# MIPI_CSI-2.net
KiCad netlist of a schematic drawn in Altium Designer
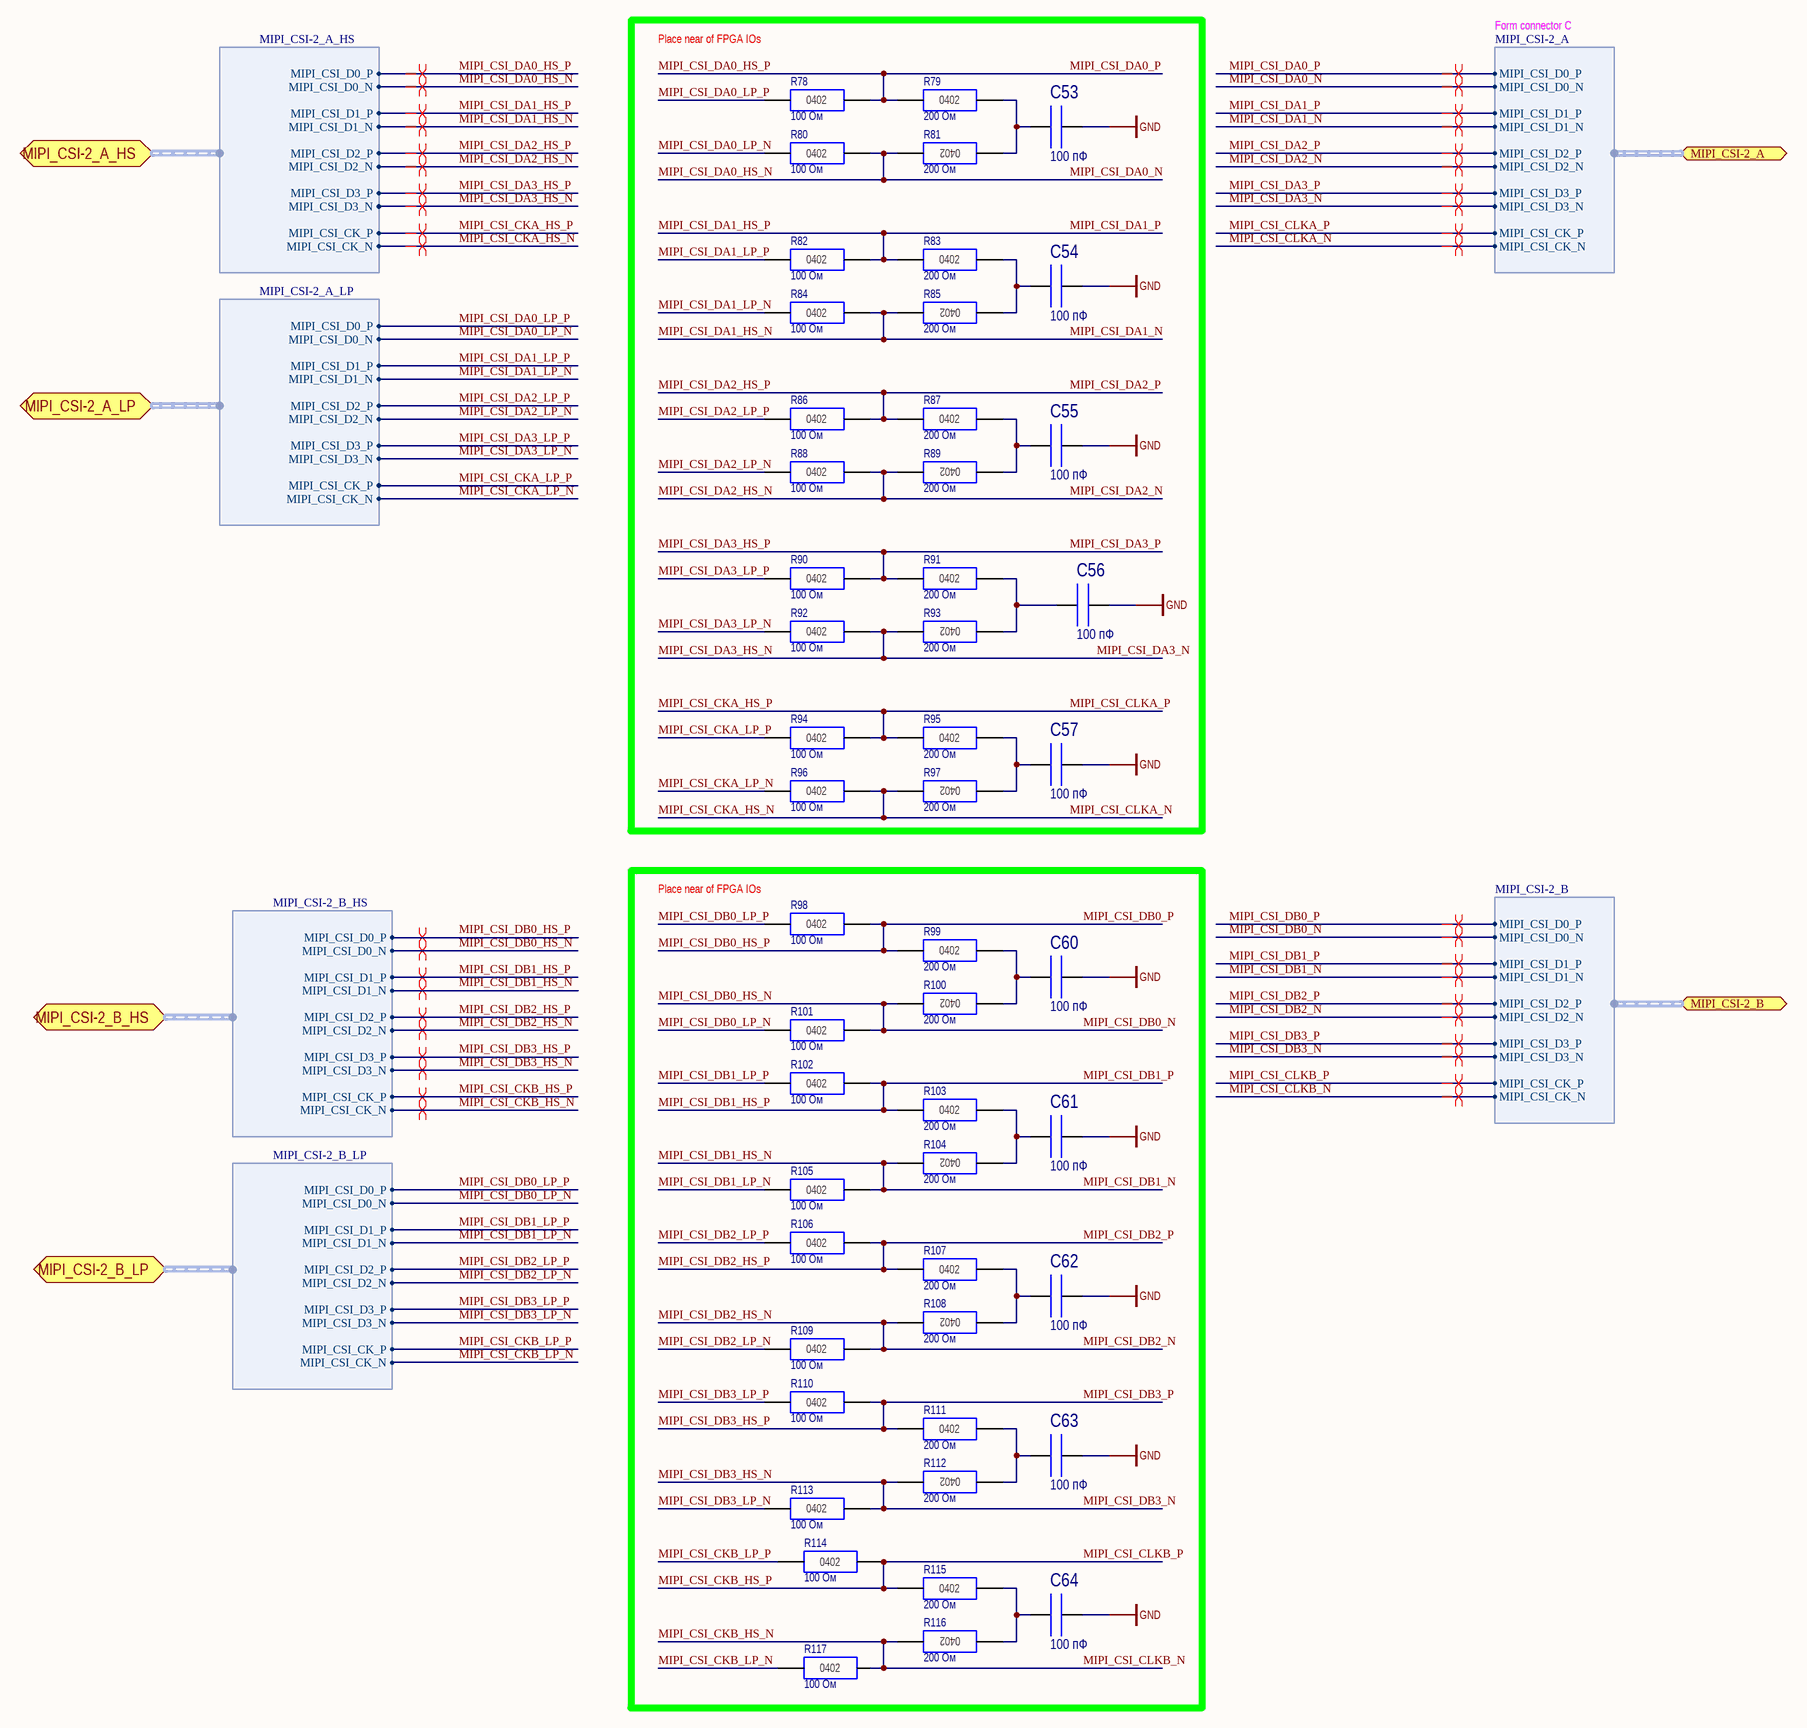
[diagram p0: MIPI_CSI-2.SchDoc]

(export (version "E")
  (design (tool "Eeschema 10.0.6"))
  (components
    (comp (ref "C53")
      (value "100 пФ")
      (footprint "CC0402(1005)")
      (description "Чип конденсатор керамический")
      (fields (field (name "Comment") "CC0402-NP0-100 пФ-1%-50В"))
      (libsource (lib "Чип конденсаторы") (part "CC0402-X7R-#-20%-10В"))
    )
    (comp (ref "C54")
      (value "100 пФ")
      (footprint "CC0402(1005)")
      (description "Чип конденсатор керамический")
      (fields (field (name "Comment") "CC0402-NP0-100 пФ-1%-50В"))
      (libsource (lib "Чип конденсаторы") (part "CC0402-X7R-#-20%-10В"))
    )
    (comp (ref "C55")
      (value "100 пФ")
      (footprint "CC0402(1005)")
      (description "Чип конденсатор керамический")
      (fields (field (name "Comment") "CC0402-NP0-100 пФ-1%-50В"))
      (libsource (lib "Чип конденсаторы") (part "CC0402-X7R-#-20%-10В"))
    )
    (comp (ref "C56")
      (value "100 пФ")
      (footprint "CC0402(1005)")
      (description "Чип конденсатор керамический")
      (fields (field (name "Comment") "CC0402-NP0-100 пФ-1%-50В"))
      (libsource (lib "Чип конденсаторы") (part "CC0402-X7R-#-20%-10В"))
    )
    (comp (ref "C57")
      (value "100 пФ")
      (footprint "CC0402(1005)")
      (description "Чип конденсатор керамический")
      (fields (field (name "Comment") "CC0402-NP0-100 пФ-1%-50В"))
      (libsource (lib "Чип конденсаторы") (part "CC0402-X7R-#-20%-10В"))
    )
    (comp (ref "C60")
      (value "100 пФ")
      (footprint "CC0402(1005)")
      (description "Чип конденсатор керамический")
      (fields (field (name "Comment") "CC0402-NP0-100 пФ-1%-50В"))
      (libsource (lib "Чип конденсаторы") (part "CC0402-X7R-#-20%-10В"))
    )
    (comp (ref "C61")
      (value "100 пФ")
      (footprint "CC0402(1005)")
      (description "Чип конденсатор керамический")
      (fields (field (name "Comment") "CC0402-NP0-100 пФ-1%-50В"))
      (libsource (lib "Чип конденсаторы") (part "CC0402-X7R-#-20%-10В"))
    )
    (comp (ref "C62")
      (value "100 пФ")
      (footprint "CC0402(1005)")
      (description "Чип конденсатор керамический")
      (fields (field (name "Comment") "CC0402-NP0-100 пФ-1%-50В"))
      (libsource (lib "Чип конденсаторы") (part "CC0402-X7R-#-20%-10В"))
    )
    (comp (ref "C63")
      (value "100 пФ")
      (footprint "CC0402(1005)")
      (description "Чип конденсатор керамический")
      (fields (field (name "Comment") "CC0402-NP0-100 пФ-1%-50В"))
      (libsource (lib "Чип конденсаторы") (part "CC0402-X7R-#-20%-10В"))
    )
    (comp (ref "C64")
      (value "100 пФ")
      (footprint "CC0402(1005)")
      (description "Чип конденсатор керамический")
      (fields (field (name "Comment") "CC0402-NP0-100 пФ-1%-50В"))
      (libsource (lib "Чип конденсаторы") (part "CC0402-X7R-#-20%-10В"))
    )
    (comp (ref "R78")
      (value "100 Ом")
      (footprint "CR0402(1005)")
      (description "Чип резистор")
      (fields (field (name "TOLERANCE") "5%") (field (name "Comment") "CR0402-100 Ом-±5%"))
      (libsource (lib "") (part "CR0402-#-±5%_1"))
    )
    (comp (ref "R79")
      (value "200 Ом")
      (footprint "CR0402(1005)")
      (description "Чип резистор")
      (fields (field (name "TOLERANCE") "5%") (field (name "Comment") "CR0402-200 Ом-±5%"))
      (libsource (lib "") (part "CR0402-#-±5%_1"))
    )
    (comp (ref "R80")
      (value "100 Ом")
      (footprint "CR0402(1005)")
      (description "Чип резистор")
      (fields (field (name "TOLERANCE") "5%") (field (name "Comment") "CR0402-100 Ом-±5%"))
      (libsource (lib "") (part "CR0402-#-±5%_1"))
    )
    (comp (ref "R81")
      (value "200 Ом")
      (footprint "CR0402(1005)")
      (description "Чип резистор")
      (fields (field (name "TOLERANCE") "5%") (field (name "Comment") "CR0402-200 Ом-±5%"))
      (libsource (lib "Резисторы") (part "CR0402-#-±5%"))
    )
    (comp (ref "R82")
      (value "100 Ом")
      (footprint "CR0402(1005)")
      (description "Чип резистор")
      (fields (field (name "TOLERANCE") "5%") (field (name "Comment") "CR0402-100 Ом-±5%"))
      (libsource (lib "") (part "CR0402-#-±5%_1"))
    )
    (comp (ref "R83")
      (value "200 Ом")
      (footprint "CR0402(1005)")
      (description "Чип резистор")
      (fields (field (name "TOLERANCE") "5%") (field (name "Comment") "CR0402-200 Ом-±5%"))
      (libsource (lib "") (part "CR0402-#-±5%_1"))
    )
    (comp (ref "R84")
      (value "100 Ом")
      (footprint "CR0402(1005)")
      (description "Чип резистор")
      (fields (field (name "TOLERANCE") "5%") (field (name "Comment") "CR0402-100 Ом-±5%"))
      (libsource (lib "") (part "CR0402-#-±5%_1"))
    )
    (comp (ref "R85")
      (value "200 Ом")
      (footprint "CR0402(1005)")
      (description "Чип резистор")
      (fields (field (name "TOLERANCE") "5%") (field (name "Comment") "CR0402-200 Ом-±5%"))
      (libsource (lib "Резисторы") (part "CR0402-#-±5%"))
    )
    (comp (ref "R86")
      (value "100 Ом")
      (footprint "CR0402(1005)")
      (description "Чип резистор")
      (fields (field (name "TOLERANCE") "5%") (field (name "Comment") "CR0402-100 Ом-±5%"))
      (libsource (lib "") (part "CR0402-#-±5%_1"))
    )
    (comp (ref "R87")
      (value "200 Ом")
      (footprint "CR0402(1005)")
      (description "Чип резистор")
      (fields (field (name "TOLERANCE") "5%") (field (name "Comment") "CR0402-200 Ом-±5%"))
      (libsource (lib "") (part "CR0402-#-±5%_1"))
    )
    (comp (ref "R88")
      (value "100 Ом")
      (footprint "CR0402(1005)")
      (description "Чип резистор")
      (fields (field (name "TOLERANCE") "5%") (field (name "Comment") "CR0402-100 Ом-±5%"))
      (libsource (lib "") (part "CR0402-#-±5%_1"))
    )
    (comp (ref "R89")
      (value "200 Ом")
      (footprint "CR0402(1005)")
      (description "Чип резистор")
      (fields (field (name "TOLERANCE") "5%") (field (name "Comment") "CR0402-200 Ом-±5%"))
      (libsource (lib "Резисторы") (part "CR0402-#-±5%"))
    )
    (comp (ref "R90")
      (value "100 Ом")
      (footprint "CR0402(1005)")
      (description "Чип резистор")
      (fields (field (name "TOLERANCE") "5%") (field (name "Comment") "CR0402-100 Ом-±5%"))
      (libsource (lib "") (part "CR0402-#-±5%_1"))
    )
    (comp (ref "R91")
      (value "200 Ом")
      (footprint "CR0402(1005)")
      (description "Чип резистор")
      (fields (field (name "TOLERANCE") "5%") (field (name "Comment") "CR0402-200 Ом-±5%"))
      (libsource (lib "") (part "CR0402-#-±5%_1"))
    )
    (comp (ref "R92")
      (value "100 Ом")
      (footprint "CR0402(1005)")
      (description "Чип резистор")
      (fields (field (name "TOLERANCE") "5%") (field (name "Comment") "CR0402-100 Ом-±5%"))
      (libsource (lib "") (part "CR0402-#-±5%_1"))
    )
    (comp (ref "R93")
      (value "200 Ом")
      (footprint "CR0402(1005)")
      (description "Чип резистор")
      (fields (field (name "TOLERANCE") "5%") (field (name "Comment") "CR0402-200 Ом-±5%"))
      (libsource (lib "Резисторы") (part "CR0402-#-±5%"))
    )
    (comp (ref "R94")
      (value "100 Ом")
      (footprint "CR0402(1005)")
      (description "Чип резистор")
      (fields (field (name "TOLERANCE") "5%") (field (name "Comment") "CR0402-100 Ом-±5%"))
      (libsource (lib "") (part "CR0402-#-±5%_1"))
    )
    (comp (ref "R95")
      (value "200 Ом")
      (footprint "CR0402(1005)")
      (description "Чип резистор")
      (fields (field (name "TOLERANCE") "5%") (field (name "Comment") "CR0402-200 Ом-±5%"))
      (libsource (lib "") (part "CR0402-#-±5%_1"))
    )
    (comp (ref "R96")
      (value "100 Ом")
      (footprint "CR0402(1005)")
      (description "Чип резистор")
      (fields (field (name "TOLERANCE") "5%") (field (name "Comment") "CR0402-100 Ом-±5%"))
      (libsource (lib "") (part "CR0402-#-±5%_1"))
    )
    (comp (ref "R97")
      (value "200 Ом")
      (footprint "CR0402(1005)")
      (description "Чип резистор")
      (fields (field (name "TOLERANCE") "5%") (field (name "Comment") "CR0402-200 Ом-±5%"))
      (libsource (lib "Резисторы") (part "CR0402-#-±5%"))
    )
    (comp (ref "R98")
      (value "100 Ом")
      (footprint "CR0402(1005)")
      (description "Чип резистор")
      (fields (field (name "TOLERANCE") "5%") (field (name "Comment") "CR0402-100 Ом-±5%"))
      (libsource (lib "") (part "CR0402-#-±5%_1"))
    )
    (comp (ref "R99")
      (value "200 Ом")
      (footprint "CR0402(1005)")
      (description "Чип резистор")
      (fields (field (name "TOLERANCE") "5%") (field (name "Comment") "CR0402-200 Ом-±5%"))
      (libsource (lib "") (part "CR0402-#-±5%_1"))
    )
    (comp (ref "R100")
      (value "200 Ом")
      (footprint "CR0402(1005)")
      (description "Чип резистор")
      (fields (field (name "TOLERANCE") "5%") (field (name "Comment") "CR0402-200 Ом-±5%"))
      (libsource (lib "Резисторы") (part "CR0402-#-±5%"))
    )
    (comp (ref "R101")
      (value "100 Ом")
      (footprint "CR0402(1005)")
      (description "Чип резистор")
      (fields (field (name "TOLERANCE") "5%") (field (name "Comment") "CR0402-100 Ом-±5%"))
      (libsource (lib "") (part "CR0402-#-±5%_1"))
    )
    (comp (ref "R102")
      (value "100 Ом")
      (footprint "CR0402(1005)")
      (description "Чип резистор")
      (fields (field (name "TOLERANCE") "5%") (field (name "Comment") "CR0402-100 Ом-±5%"))
      (libsource (lib "") (part "CR0402-#-±5%_1"))
    )
    (comp (ref "R103")
      (value "200 Ом")
      (footprint "CR0402(1005)")
      (description "Чип резистор")
      (fields (field (name "TOLERANCE") "5%") (field (name "Comment") "CR0402-200 Ом-±5%"))
      (libsource (lib "") (part "CR0402-#-±5%_1"))
    )
    (comp (ref "R104")
      (value "200 Ом")
      (footprint "CR0402(1005)")
      (description "Чип резистор")
      (fields (field (name "TOLERANCE") "5%") (field (name "Comment") "CR0402-200 Ом-±5%"))
      (libsource (lib "Резисторы") (part "CR0402-#-±5%"))
    )
    (comp (ref "R105")
      (value "100 Ом")
      (footprint "CR0402(1005)")
      (description "Чип резистор")
      (fields (field (name "TOLERANCE") "5%") (field (name "Comment") "CR0402-100 Ом-±5%"))
      (libsource (lib "") (part "CR0402-#-±5%_1"))
    )
    (comp (ref "R106")
      (value "100 Ом")
      (footprint "CR0402(1005)")
      (description "Чип резистор")
      (fields (field (name "TOLERANCE") "5%") (field (name "Comment") "CR0402-100 Ом-±5%"))
      (libsource (lib "") (part "CR0402-#-±5%_1"))
    )
    (comp (ref "R107")
      (value "200 Ом")
      (footprint "CR0402(1005)")
      (description "Чип резистор")
      (fields (field (name "TOLERANCE") "5%") (field (name "Comment") "CR0402-200 Ом-±5%"))
      (libsource (lib "") (part "CR0402-#-±5%_1"))
    )
    (comp (ref "R108")
      (value "200 Ом")
      (footprint "CR0402(1005)")
      (description "Чип резистор")
      (fields (field (name "TOLERANCE") "5%") (field (name "Comment") "CR0402-200 Ом-±5%"))
      (libsource (lib "Резисторы") (part "CR0402-#-±5%"))
    )
    (comp (ref "R109")
      (value "100 Ом")
      (footprint "CR0402(1005)")
      (description "Чип резистор")
      (fields (field (name "TOLERANCE") "5%") (field (name "Comment") "CR0402-100 Ом-±5%"))
      (libsource (lib "") (part "CR0402-#-±5%_1"))
    )
    (comp (ref "R110")
      (value "100 Ом")
      (footprint "CR0402(1005)")
      (description "Чип резистор")
      (fields (field (name "TOLERANCE") "5%") (field (name "Comment") "CR0402-100 Ом-±5%"))
      (libsource (lib "") (part "CR0402-#-±5%_1"))
    )
    (comp (ref "R111")
      (value "200 Ом")
      (footprint "CR0402(1005)")
      (description "Чип резистор")
      (fields (field (name "TOLERANCE") "5%") (field (name "Comment") "CR0402-200 Ом-±5%"))
      (libsource (lib "") (part "CR0402-#-±5%_1"))
    )
    (comp (ref "R112")
      (value "200 Ом")
      (footprint "CR0402(1005)")
      (description "Чип резистор")
      (fields (field (name "TOLERANCE") "5%") (field (name "Comment") "CR0402-200 Ом-±5%"))
      (libsource (lib "Резисторы") (part "CR0402-#-±5%"))
    )
    (comp (ref "R113")
      (value "100 Ом")
      (footprint "CR0402(1005)")
      (description "Чип резистор")
      (fields (field (name "TOLERANCE") "5%") (field (name "Comment") "CR0402-100 Ом-±5%"))
      (libsource (lib "") (part "CR0402-#-±5%_1"))
    )
    (comp (ref "R114")
      (value "100 Ом")
      (footprint "CR0402(1005)")
      (description "Чип резистор")
      (fields (field (name "TOLERANCE") "5%") (field (name "Comment") "CR0402-100 Ом-±5%"))
      (libsource (lib "") (part "CR0402-#-±5%_1"))
    )
    (comp (ref "R115")
      (value "200 Ом")
      (footprint "CR0402(1005)")
      (description "Чип резистор")
      (fields (field (name "TOLERANCE") "5%") (field (name "Comment") "CR0402-200 Ом-±5%"))
      (libsource (lib "") (part "CR0402-#-±5%_1"))
    )
    (comp (ref "R116")
      (value "200 Ом")
      (footprint "CR0402(1005)")
      (description "Чип резистор")
      (fields (field (name "TOLERANCE") "5%") (field (name "Comment") "CR0402-200 Ом-±5%"))
      (libsource (lib "Резисторы") (part "CR0402-#-±5%"))
    )
    (comp (ref "R117")
      (value "100 Ом")
      (footprint "CR0402(1005)")
      (description "Чип резистор")
      (fields (field (name "TOLERANCE") "5%") (field (name "Comment") "CR0402-100 Ом-±5%"))
      (libsource (lib "") (part "CR0402-#-±5%_1"))
    )
  )
  (nets
    (net (code "7") (name "/MIPI_CSI_CKA_HS_N") (class "Default")
      (node (ref "R96") (pin "2") (pinfunction "-_2") (pintype "passive"))
      (node (ref "R97") (pin "2") (pinfunction "-_2") (pintype "passive"))
    )
    (net (code "8") (name "/MIPI_CSI_CKA_HS_P") (class "Default")
      (node (ref "R94") (pin "2") (pinfunction "-_2") (pintype "passive"))
      (node (ref "R95") (pin "1") (pinfunction "+_1") (pintype "passive"))
    )
    (net (code "9") (name "/MIPI_CSI_CKA_LP_N") (class "Default")
      (node (ref "R96") (pin "1") (pinfunction "+_1") (pintype "passive"))
    )
    (net (code "10") (name "/MIPI_CSI_CKA_LP_P") (class "Default")
      (node (ref "R94") (pin "1") (pinfunction "+_1") (pintype "passive"))
    )
    (net (code "11") (name "/MIPI_CSI_CKB_HS_N") (class "Default")
      (node (ref "R116") (pin "2") (pinfunction "-_2") (pintype "passive"))
      (node (ref "R117") (pin "2") (pinfunction "-_2") (pintype "passive"))
    )
    (net (code "12") (name "/MIPI_CSI_CKB_HS_P") (class "Default")
      (node (ref "R114") (pin "2") (pinfunction "-_2") (pintype "passive"))
      (node (ref "R115") (pin "1") (pinfunction "+_1") (pintype "passive"))
    )
    (net (code "13") (name "/MIPI_CSI_CKB_LP_N") (class "Default")
      (node (ref "R117") (pin "1") (pinfunction "+_1") (pintype "passive"))
    )
    (net (code "14") (name "/MIPI_CSI_CKB_LP_P") (class "Default")
      (node (ref "R114") (pin "1") (pinfunction "+_1") (pintype "passive"))
    )
    (net (code "15") (name "/MIPI_CSI_DA0_HS_N") (class "Default")
      (node (ref "R80") (pin "2") (pinfunction "-_2") (pintype "passive"))
      (node (ref "R81") (pin "2") (pinfunction "-_2") (pintype "passive"))
    )
    (net (code "16") (name "/MIPI_CSI_DA0_HS_P") (class "Default")
      (node (ref "R78") (pin "2") (pinfunction "-_2") (pintype "passive"))
      (node (ref "R79") (pin "1") (pinfunction "+_1") (pintype "passive"))
    )
    (net (code "17") (name "/MIPI_CSI_DA0_LP_N") (class "Default")
      (node (ref "R80") (pin "1") (pinfunction "+_1") (pintype "passive"))
    )
    (net (code "18") (name "/MIPI_CSI_DA0_LP_P") (class "Default")
      (node (ref "R78") (pin "1") (pinfunction "+_1") (pintype "passive"))
    )
    (net (code "19") (name "/MIPI_CSI_DA1_HS_N") (class "Default")
      (node (ref "R84") (pin "2") (pinfunction "-_2") (pintype "passive"))
      (node (ref "R85") (pin "2") (pinfunction "-_2") (pintype "passive"))
    )
    (net (code "20") (name "/MIPI_CSI_DA1_HS_P") (class "Default")
      (node (ref "R82") (pin "2") (pinfunction "-_2") (pintype "passive"))
      (node (ref "R83") (pin "1") (pinfunction "+_1") (pintype "passive"))
    )
    (net (code "21") (name "/MIPI_CSI_DA1_LP_N") (class "Default")
      (node (ref "R84") (pin "1") (pinfunction "+_1") (pintype "passive"))
    )
    (net (code "22") (name "/MIPI_CSI_DA1_LP_P") (class "Default")
      (node (ref "R82") (pin "1") (pinfunction "+_1") (pintype "passive"))
    )
    (net (code "23") (name "/MIPI_CSI_DA2_HS_N") (class "Default")
      (node (ref "R88") (pin "2") (pinfunction "-_2") (pintype "passive"))
      (node (ref "R89") (pin "2") (pinfunction "-_2") (pintype "passive"))
    )
    (net (code "24") (name "/MIPI_CSI_DA2_HS_P") (class "Default")
      (node (ref "R86") (pin "2") (pinfunction "-_2") (pintype "passive"))
      (node (ref "R87") (pin "1") (pinfunction "+_1") (pintype "passive"))
    )
    (net (code "25") (name "/MIPI_CSI_DA2_LP_N") (class "Default")
      (node (ref "R88") (pin "1") (pinfunction "+_1") (pintype "passive"))
    )
    (net (code "26") (name "/MIPI_CSI_DA2_LP_P") (class "Default")
      (node (ref "R86") (pin "1") (pinfunction "+_1") (pintype "passive"))
    )
    (net (code "27") (name "/MIPI_CSI_DA3_HS_N") (class "Default")
      (node (ref "R92") (pin "2") (pinfunction "-_2") (pintype "passive"))
      (node (ref "R93") (pin "2") (pinfunction "-_2") (pintype "passive"))
    )
    (net (code "28") (name "/MIPI_CSI_DA3_HS_P") (class "Default")
      (node (ref "R90") (pin "2") (pinfunction "-_2") (pintype "passive"))
      (node (ref "R91") (pin "1") (pinfunction "+_1") (pintype "passive"))
    )
    (net (code "29") (name "/MIPI_CSI_DA3_LP_N") (class "Default")
      (node (ref "R92") (pin "1") (pinfunction "+_1") (pintype "passive"))
    )
    (net (code "30") (name "/MIPI_CSI_DA3_LP_P") (class "Default")
      (node (ref "R90") (pin "1") (pinfunction "+_1") (pintype "passive"))
    )
    (net (code "31") (name "/MIPI_CSI_DB0_HS_N") (class "Default")
      (node (ref "R100") (pin "2") (pinfunction "-_2") (pintype "passive"))
      (node (ref "R101") (pin "2") (pinfunction "-_2") (pintype "passive"))
    )
    (net (code "32") (name "/MIPI_CSI_DB0_HS_P") (class "Default")
      (node (ref "R98") (pin "2") (pinfunction "-_2") (pintype "passive"))
      (node (ref "R99") (pin "1") (pinfunction "+_1") (pintype "passive"))
    )
    (net (code "33") (name "/MIPI_CSI_DB0_LP_N") (class "Default")
      (node (ref "R101") (pin "1") (pinfunction "+_1") (pintype "passive"))
    )
    (net (code "34") (name "/MIPI_CSI_DB0_LP_P") (class "Default")
      (node (ref "R98") (pin "1") (pinfunction "+_1") (pintype "passive"))
    )
    (net (code "35") (name "/MIPI_CSI_DB1_HS_N") (class "Default")
      (node (ref "R104") (pin "2") (pinfunction "-_2") (pintype "passive"))
      (node (ref "R105") (pin "2") (pinfunction "-_2") (pintype "passive"))
    )
    (net (code "36") (name "/MIPI_CSI_DB1_HS_P") (class "Default")
      (node (ref "R102") (pin "2") (pinfunction "-_2") (pintype "passive"))
      (node (ref "R103") (pin "1") (pinfunction "+_1") (pintype "passive"))
    )
    (net (code "37") (name "/MIPI_CSI_DB1_LP_N") (class "Default")
      (node (ref "R105") (pin "1") (pinfunction "+_1") (pintype "passive"))
    )
    (net (code "38") (name "/MIPI_CSI_DB1_LP_P") (class "Default")
      (node (ref "R102") (pin "1") (pinfunction "+_1") (pintype "passive"))
    )
    (net (code "39") (name "/MIPI_CSI_DB2_HS_N") (class "Default")
      (node (ref "R108") (pin "2") (pinfunction "-_2") (pintype "passive"))
      (node (ref "R109") (pin "2") (pinfunction "-_2") (pintype "passive"))
    )
    (net (code "40") (name "/MIPI_CSI_DB2_HS_P") (class "Default")
      (node (ref "R106") (pin "2") (pinfunction "-_2") (pintype "passive"))
      (node (ref "R107") (pin "1") (pinfunction "+_1") (pintype "passive"))
    )
    (net (code "41") (name "/MIPI_CSI_DB2_LP_N") (class "Default")
      (node (ref "R109") (pin "1") (pinfunction "+_1") (pintype "passive"))
    )
    (net (code "42") (name "/MIPI_CSI_DB2_LP_P") (class "Default")
      (node (ref "R106") (pin "1") (pinfunction "+_1") (pintype "passive"))
    )
    (net (code "43") (name "/MIPI_CSI_DB3_HS_N") (class "Default")
      (node (ref "R112") (pin "2") (pinfunction "-_2") (pintype "passive"))
      (node (ref "R113") (pin "2") (pinfunction "-_2") (pintype "passive"))
    )
    (net (code "44") (name "/MIPI_CSI_DB3_HS_P") (class "Default")
      (node (ref "R110") (pin "2") (pinfunction "-_2") (pintype "passive"))
      (node (ref "R111") (pin "1") (pinfunction "+_1") (pintype "passive"))
    )
    (net (code "45") (name "/MIPI_CSI_DB3_LP_N") (class "Default")
      (node (ref "R113") (pin "1") (pinfunction "+_1") (pintype "passive"))
    )
    (net (code "46") (name "/MIPI_CSI_DB3_LP_P") (class "Default")
      (node (ref "R110") (pin "1") (pinfunction "+_1") (pintype "passive"))
    )
    (net (code "53") (name "GND") (class "Default")
      (node (ref "C53") (pin "1") (pinfunction "+_1") (pintype "passive"))
      (node (ref "C54") (pin "1") (pinfunction "+_1") (pintype "passive"))
      (node (ref "C55") (pin "1") (pinfunction "+_1") (pintype "passive"))
      (node (ref "C56") (pin "1") (pinfunction "+_1") (pintype "passive"))
      (node (ref "C57") (pin "1") (pinfunction "+_1") (pintype "passive"))
      (node (ref "C60") (pin "1") (pinfunction "+_1") (pintype "passive"))
      (node (ref "C61") (pin "1") (pinfunction "+_1") (pintype "passive"))
      (node (ref "C62") (pin "1") (pinfunction "+_1") (pintype "passive"))
      (node (ref "C63") (pin "1") (pinfunction "+_1") (pintype "passive"))
      (node (ref "C64") (pin "1") (pinfunction "+_1") (pintype "passive"))
    )
    (net (code "54") (name "Net-(C53--)") (class "Default")
      (node (ref "C53") (pin "2") (pinfunction "-_2") (pintype "passive"))
      (node (ref "R79") (pin "2") (pinfunction "-_2") (pintype "passive"))
      (node (ref "R81") (pin "1") (pinfunction "+_1") (pintype "passive"))
    )
    (net (code "55") (name "Net-(C54--)") (class "Default")
      (node (ref "C54") (pin "2") (pinfunction "-_2") (pintype "passive"))
      (node (ref "R83") (pin "2") (pinfunction "-_2") (pintype "passive"))
      (node (ref "R85") (pin "1") (pinfunction "+_1") (pintype "passive"))
    )
    (net (code "56") (name "Net-(C55--)") (class "Default")
      (node (ref "C55") (pin "2") (pinfunction "-_2") (pintype "passive"))
      (node (ref "R87") (pin "2") (pinfunction "-_2") (pintype "passive"))
      (node (ref "R89") (pin "1") (pinfunction "+_1") (pintype "passive"))
    )
    (net (code "57") (name "Net-(C56--)") (class "Default")
      (node (ref "C56") (pin "2") (pinfunction "-_2") (pintype "passive"))
      (node (ref "R91") (pin "2") (pinfunction "-_2") (pintype "passive"))
      (node (ref "R93") (pin "1") (pinfunction "+_1") (pintype "passive"))
    )
    (net (code "58") (name "Net-(C57--)") (class "Default")
      (node (ref "C57") (pin "2") (pinfunction "-_2") (pintype "passive"))
      (node (ref "R95") (pin "2") (pinfunction "-_2") (pintype "passive"))
      (node (ref "R97") (pin "1") (pinfunction "+_1") (pintype "passive"))
    )
    (net (code "59") (name "Net-(C60--)") (class "Default")
      (node (ref "C60") (pin "2") (pinfunction "-_2") (pintype "passive"))
      (node (ref "R100") (pin "1") (pinfunction "+_1") (pintype "passive"))
      (node (ref "R99") (pin "2") (pinfunction "-_2") (pintype "passive"))
    )
    (net (code "60") (name "Net-(C61--)") (class "Default")
      (node (ref "C61") (pin "2") (pinfunction "-_2") (pintype "passive"))
      (node (ref "R103") (pin "2") (pinfunction "-_2") (pintype "passive"))
      (node (ref "R104") (pin "1") (pinfunction "+_1") (pintype "passive"))
    )
    (net (code "61") (name "Net-(C62--)") (class "Default")
      (node (ref "C62") (pin "2") (pinfunction "-_2") (pintype "passive"))
      (node (ref "R107") (pin "2") (pinfunction "-_2") (pintype "passive"))
      (node (ref "R108") (pin "1") (pinfunction "+_1") (pintype "passive"))
    )
    (net (code "62") (name "Net-(C63--)") (class "Default")
      (node (ref "C63") (pin "2") (pinfunction "-_2") (pintype "passive"))
      (node (ref "R111") (pin "2") (pinfunction "-_2") (pintype "passive"))
      (node (ref "R112") (pin "1") (pinfunction "+_1") (pintype "passive"))
    )
    (net (code "63") (name "Net-(C64--)") (class "Default")
      (node (ref "C64") (pin "2") (pinfunction "-_2") (pintype "passive"))
      (node (ref "R115") (pin "2") (pinfunction "-_2") (pintype "passive"))
      (node (ref "R116") (pin "1") (pinfunction "+_1") (pintype "passive"))
    )
  )
)
